# Main.net
KiCad netlist of a schematic drawn in Altium Designer
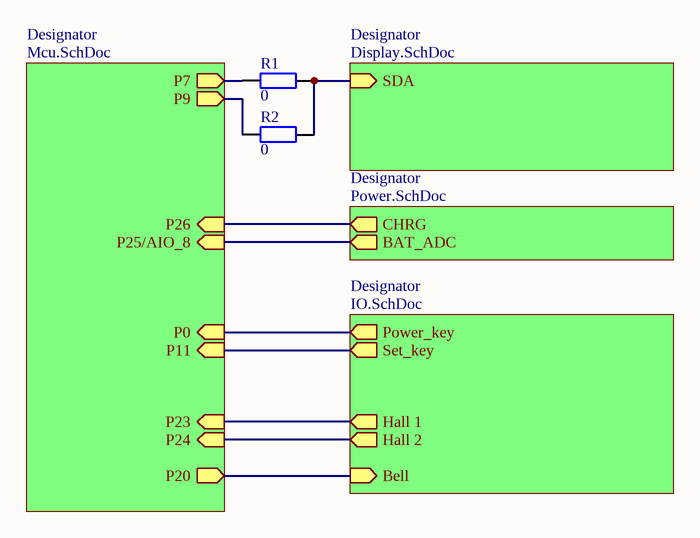
[diagram p0: Main.SchDoc]

(export (version "E")
  (design (tool "Eeschema 10.0.6"))
  (components
    (comp (ref "R1")
      (value "0")
      (description "Resistor")
      (fields (field (name "PUBLISHER") "Altium Limited"))
      (libsource (lib "Miscellaneous Devices") (part "Res2"))
    )
    (comp (ref "R2")
      (value "0")
      (description "Resistor")
      (fields (field (name "PUBLISHER") "Altium Limited"))
      (libsource (lib "Miscellaneous Devices") (part "Res2"))
    )
  )
  (nets
    (net (code "5") (name "/P7") (class "Default")
      (node (ref "R1") (pin "2") (pinfunction "2_2") (pintype "passive"))
    )
    (net (code "6") (name "/P9") (class "Default")
      (node (ref "R2") (pin "2") (pinfunction "2_2") (pintype "passive"))
    )
    (net (code "9") (name "/SDA") (class "Default")
      (node (ref "R1") (pin "1") (pinfunction "1_1") (pintype "passive"))
      (node (ref "R2") (pin "1") (pinfunction "1_1") (pintype "passive"))
    )
  )
)
